# Morpheus_LED1.net
KiCad netlist of a schematic drawn in Altium Designer
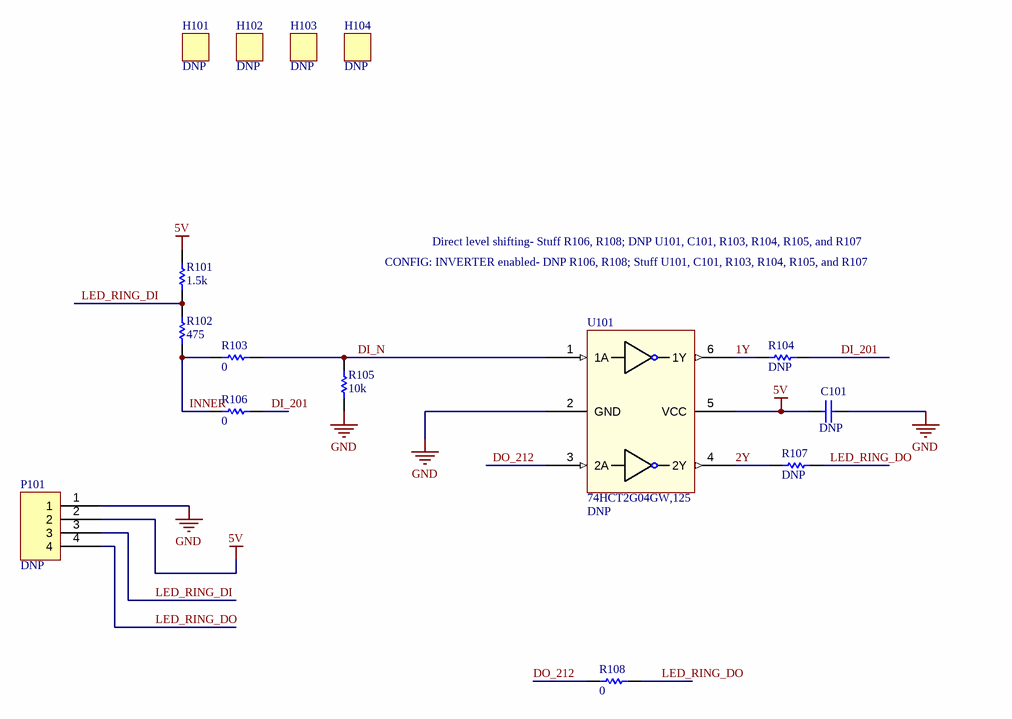
[diagram p0: Morpheus_LED1.SchDoc]

(export (version "E")
  (design (tool "Eeschema 10.0.6"))
  (components
    (comp (ref "C101")
      (value "DNP")
      (footprint "CAP0402_SENSE_DVT")
      (description "CAP CER 0.1UF 50V 10% X7R 0402")
      (fields (field (name "TOLERANCE") "10%") (field (name "VOLTAGE") "50V"))
      (libsource (lib "Morpheus_pill") (part "C_0.1u_10_50_X7R_0402"))
    )
    (comp (ref "H101")
      (value "DNP")
      (footprint "HOLE_ROUND_1.8mm")
      (description "general purpose hole")
      (libsource (lib "Morpheus_pill") (part "Hole"))
    )
    (comp (ref "H102")
      (value "DNP")
      (footprint "HOLE_ROUND_1.8mm")
      (description "general purpose hole")
      (libsource (lib "Morpheus_pill") (part "Hole"))
    )
    (comp (ref "H103")
      (value "DNP")
      (footprint "HOLE_ROUND_1.8mm")
      (description "general purpose hole")
      (libsource (lib "Morpheus_pill") (part "Hole"))
    )
    (comp (ref "H104")
      (value "DNP")
      (footprint "HOLE_ROUND_1.8mm")
      (description "general purpose hole")
      (libsource (lib "Morpheus_pill") (part "Hole"))
    )
    (comp (ref "P101")
      (value "DNP")
      (footprint "mate_for_molex_47420-0001")
      (description "Molex 4-pin spring connector 1.8 mm working height")
      (libsource (lib "Morpheus_pill") (part "mate_for_molex_47420-0001"))
    )
    (comp (ref "R101")
      (value "1.5k")
      (footprint "RES0402_SENSE_DVT")
      (description "RES SMD 1.5K OHM 5% 1/16W 0402")
      (fields (field (name "TOLERANCE") "5 %") (field (name "POWER") "1/16W"))
      (libsource (lib "Morpheus_pill") (part "R_1.5k_5_0.1_0402"))
    )
    (comp (ref "R102")
      (value "475")
      (footprint "RES0402_SENSE_DVT")
      (description "RES SMD 475 OHM 1% 1/16W 0402")
      (fields (field (name "TOLERANCE") "1 %") (field (name "POWER") "0.1 W"))
      (libsource (lib "Morpheus_pill") (part "R_475_1_0.1_0402"))
    )
    (comp (ref "R103")
      (value "0")
      (footprint "RES0402-SENSE-DVT")
      (description "RES SMD 0.0 OHM JUMPER 1/16W")
      (fields (field (name "TOLERANCE") "Jumper") (field (name "POWER") "1/16W"))
      (libsource (lib "Morpheus_pill") (part "R_0_jumper_0.1_0402"))
    )
    (comp (ref "R104")
      (value "DNP")
      (footprint "RES0402_SENSE_DVT")
      (description "RES SMD 100 OHM 1% 1/16W 0402")
      (fields (field (name "TOLERANCE") "1 %") (field (name "POWER") "1/16W"))
      (libsource (lib "Morpheus_pill") (part "R_100_1_0.1_0402"))
    )
    (comp (ref "R105")
      (value "10k")
      (footprint "RES0402_SENSE_DVT")
      (description "RES SMD 10K OHM 5% 1/16W 0402")
      (fields (field (name "TOLERANCE") "5 %") (field (name "POWER") "1/16W"))
      (libsource (lib "Morpheus_pill") (part "R_10k_5_0.1_0402"))
    )
    (comp (ref "R106")
      (value "0")
      (footprint "RES0402-SENSE-DVT")
      (description "RES SMD 0.0 OHM JUMPER 1/16W")
      (fields (field (name "TOLERANCE") "Jumper") (field (name "POWER") "1/16W"))
      (libsource (lib "Morpheus_pill") (part "R_0_jumper_0.1_0402"))
    )
    (comp (ref "R107")
      (value "DNP")
      (footprint "RES0402_SENSE_DVT")
      (description "RES SMD 100 OHM 1% 1/16W 0402")
      (fields (field (name "TOLERANCE") "1 %") (field (name "POWER") "1/16W"))
      (libsource (lib "Morpheus_pill") (part "R_100_1_0.1_0402"))
    )
    (comp (ref "R108")
      (value "0")
      (footprint "RES0402-SENSE-DVT")
      (description "RES SMD 0.0 OHM JUMPER 1/16W")
      (fields (field (name "TOLERANCE") "Jumper") (field (name "POWER") "1/16W"))
      (libsource (lib "Morpheus_pill") (part "R_0_jumper_0.1_0402"))
    )
    (comp (ref "U101")
      (value "DNP")
      (footprint "SOT65P210X110-6N")
      (description "Dual inverter The 74HC2G04; 74HCT2G04 is a high-speed Si-gate CMOS device.")
      (fields (field (name "PN") "74HCT2G04GW,125"))
      (libsource (lib "Morpheus_pill") (part "74HCT2G04"))
    )
  )
  (nets
    (net (code "1") (name "/1Y") (class "Default")
      (node (ref "R104") (pin "1") (pinfunction "1_1") (pintype "passive"))
      (node (ref "U101") (pin "6") (pinfunction "1Y_6") (pintype "output"))
    )
    (net (code "2") (name "/2Y") (class "Default")
      (node (ref "R107") (pin "1") (pinfunction "1_1") (pintype "passive"))
      (node (ref "U101") (pin "4") (pinfunction "2Y_4") (pintype "output"))
    )
    (net (code "3") (name "/DI_201") (class "Default")
      (node (ref "R104") (pin "2") (pinfunction "2_2") (pintype "passive"))
      (node (ref "R106") (pin "2") (pinfunction "2_2") (pintype "passive"))
    )
    (net (code "4") (name "/DI_N") (class "Default")
      (node (ref "R103") (pin "2") (pinfunction "2_2") (pintype "passive"))
      (node (ref "R105") (pin "2") (pinfunction "2_2") (pintype "passive"))
      (node (ref "U101") (pin "1") (pinfunction "1A_1") (pintype "input"))
    )
    (net (code "5") (name "/DO_212") (class "Default")
      (node (ref "R108") (pin "1") (pinfunction "1_1") (pintype "passive"))
      (node (ref "U101") (pin "3") (pinfunction "2A_3") (pintype "input"))
    )
    (net (code "6") (name "/INNER") (class "Default")
      (node (ref "R102") (pin "1") (pinfunction "1_1") (pintype "passive"))
      (node (ref "R103") (pin "1") (pinfunction "1_1") (pintype "passive"))
      (node (ref "R106") (pin "1") (pinfunction "1_1") (pintype "passive"))
    )
    (net (code "7") (name "/LED_RING_DI") (class "Default")
      (node (ref "P101") (pin "3") (pinfunction "3_3") (pintype "passive"))
      (node (ref "R101") (pin "1") (pinfunction "1_1") (pintype "passive"))
      (node (ref "R102") (pin "2") (pinfunction "2_2") (pintype "passive"))
    )
    (net (code "8") (name "/LED_RING_DO") (class "Default")
      (node (ref "P101") (pin "4") (pinfunction "4_4") (pintype "passive"))
      (node (ref "R107") (pin "2") (pinfunction "2_2") (pintype "passive"))
      (node (ref "R108") (pin "2") (pinfunction "2_2") (pintype "passive"))
    )
    (net (code "9") (name "5V") (class "Default")
      (node (ref "C101") (pin "1") (pinfunction "1_1") (pintype "passive"))
      (node (ref "P101") (pin "2") (pinfunction "2_2") (pintype "passive"))
      (node (ref "R101") (pin "2") (pinfunction "2_2") (pintype "passive"))
      (node (ref "U101") (pin "5") (pinfunction "VCC_5") (pintype "power_in"))
    )
    (net (code "10") (name "GND") (class "Default")
      (node (ref "C101") (pin "2") (pinfunction "2_2") (pintype "passive"))
      (node (ref "P101") (pin "1") (pinfunction "1_1") (pintype "passive"))
      (node (ref "R105") (pin "1") (pinfunction "1_1") (pintype "passive"))
      (node (ref "U101") (pin "2") (pinfunction "GND_2") (pintype "power_in"))
    )
  )
)
